# Led_Flip_Flop.net
KiCad netlist of a schematic drawn in EAGLE
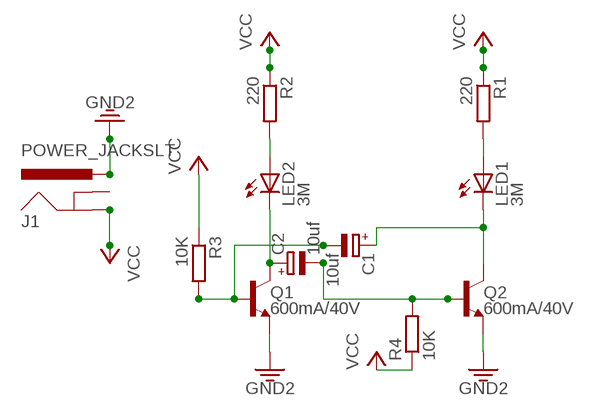
[diagram p0: schematic, sheet 1]

(export (version "E")
  (design (tool "Eeschema 10.0.6"))
  (components
    (comp (ref "C1")
      (value "10uf")
      (footprint "eagle-import:E1,8-4")
      (libsource (lib "eagle-import") (part "CPOL-EUE1.8-4"))
    )
    (comp (ref "C2")
      (value "10uf")
      (footprint "eagle-import:E1,8-4")
      (libsource (lib "eagle-import") (part "CPOL-EUE1.8-4"))
    )
    (comp (ref "J1")
      (value "POWER_JACKSLT")
      (footprint "eagle-import:POWER_JACK_SLOT")
      (libsource (lib "eagle-import") (part "POWER_JACKSLT"))
    )
    (comp (ref "LED1")
      (value "3M")
      (footprint "eagle-import:LED5MM")
      (libsource (lib "eagle-import") (part "LED5MM"))
    )
    (comp (ref "LED2")
      (value "3M")
      (footprint "eagle-import:LED5MM")
      (libsource (lib "eagle-import") (part "LED5MM"))
    )
    (comp (ref "Q1")
      (value "600mA/40V")
      (footprint "eagle-import:TO-92")
      (libsource (lib "eagle-import") (part "TRANS_NPN-P2N2222A"))
    )
    (comp (ref "Q2")
      (value "600mA/40V")
      (footprint "eagle-import:TO-92")
      (libsource (lib "eagle-import") (part "TRANS_NPN-P2N2222A"))
    )
    (comp (ref "R1")
      (value "220")
      (footprint "eagle-import:0207_10")
      (libsource (lib "eagle-import") (part "R-EU_0207/10"))
    )
    (comp (ref "R2")
      (value "220")
      (footprint "eagle-import:0207_10")
      (libsource (lib "eagle-import") (part "R-EU_0207/10"))
    )
    (comp (ref "R3")
      (value "10K")
      (footprint "eagle-import:0207_10")
      (libsource (lib "eagle-import") (part "R-EU_0207/10"))
    )
    (comp (ref "R4")
      (value "10K")
      (footprint "eagle-import:0207_10")
      (libsource (lib "eagle-import") (part "R-EU_0207/10"))
    )
  )
  (nets
    (net (code "1") (name "GND2") (class "Default")
      (node (ref "J1") (pin "PWR") (pinfunction "PWR_PWR") (pintype "bidirectional"))
      (node (ref "Q1") (pin "3") (pinfunction "E_3") (pintype "passive"))
      (node (ref "Q2") (pin "3") (pinfunction "E_3") (pintype "passive"))
    )
    (net (code "2") (name "Net-(LED1-C)") (class "Default")
      (node (ref "C1") (pin "+") (pinfunction "+_+") (pintype "passive"))
      (node (ref "LED1") (pin "K") (pinfunction "C_K") (pintype "passive"))
      (node (ref "Q2") (pin "1") (pinfunction "C_1") (pintype "passive"))
    )
    (net (code "3") (name "Net-(LED1-PadA)") (class "Default")
      (node (ref "LED1") (pin "A") (pinfunction "A_A") (pintype "passive"))
      (node (ref "R1") (pin "2") (pinfunction "2_2") (pintype "passive"))
    )
    (net (code "4") (name "Net-(LED2-C)") (class "Default")
      (node (ref "C2") (pin "+") (pinfunction "+_+") (pintype "passive"))
      (node (ref "LED2") (pin "K") (pinfunction "C_K") (pintype "passive"))
      (node (ref "Q1") (pin "1") (pinfunction "C_1") (pintype "passive"))
    )
    (net (code "5") (name "Net-(LED2-PadA)") (class "Default")
      (node (ref "LED2") (pin "A") (pinfunction "A_A") (pintype "passive"))
      (node (ref "R2") (pin "2") (pinfunction "2_2") (pintype "passive"))
    )
    (net (code "6") (name "Net-(Q1-B)") (class "Default")
      (node (ref "C1") (pin "-") (pinfunction "-_-") (pintype "passive"))
      (node (ref "Q1") (pin "2") (pinfunction "B_2") (pintype "passive"))
      (node (ref "R3") (pin "2") (pinfunction "2_2") (pintype "passive"))
    )
    (net (code "7") (name "Net-(Q2-B)") (class "Default")
      (node (ref "C2") (pin "-") (pinfunction "-_-") (pintype "passive"))
      (node (ref "Q2") (pin "2") (pinfunction "B_2") (pintype "passive"))
      (node (ref "R4") (pin "2") (pinfunction "2_2") (pintype "passive"))
    )
    (net (code "8") (name "VCC") (class "Default")
      (node (ref "J1") (pin "GND@2") (pinfunction "GND_GND@2") (pintype "bidirectional"))
      (node (ref "R1") (pin "1") (pinfunction "1_1") (pintype "passive"))
      (node (ref "R2") (pin "1") (pinfunction "1_1") (pintype "passive"))
      (node (ref "R3") (pin "1") (pinfunction "1_1") (pintype "passive"))
      (node (ref "R4") (pin "1") (pinfunction "1_1") (pintype "passive"))
    )
    (net (code "9") (name "unconnected-(J1-GNDBREAK-PadGND@1)") (class "Default")
      (node (ref "J1") (pin "GND@1") (pinfunction "GNDBREAK_GND@1") (pintype "bidirectional"))
    )
  )
)
